# v1.net
KiCad netlist of a schematic drawn in EAGLE
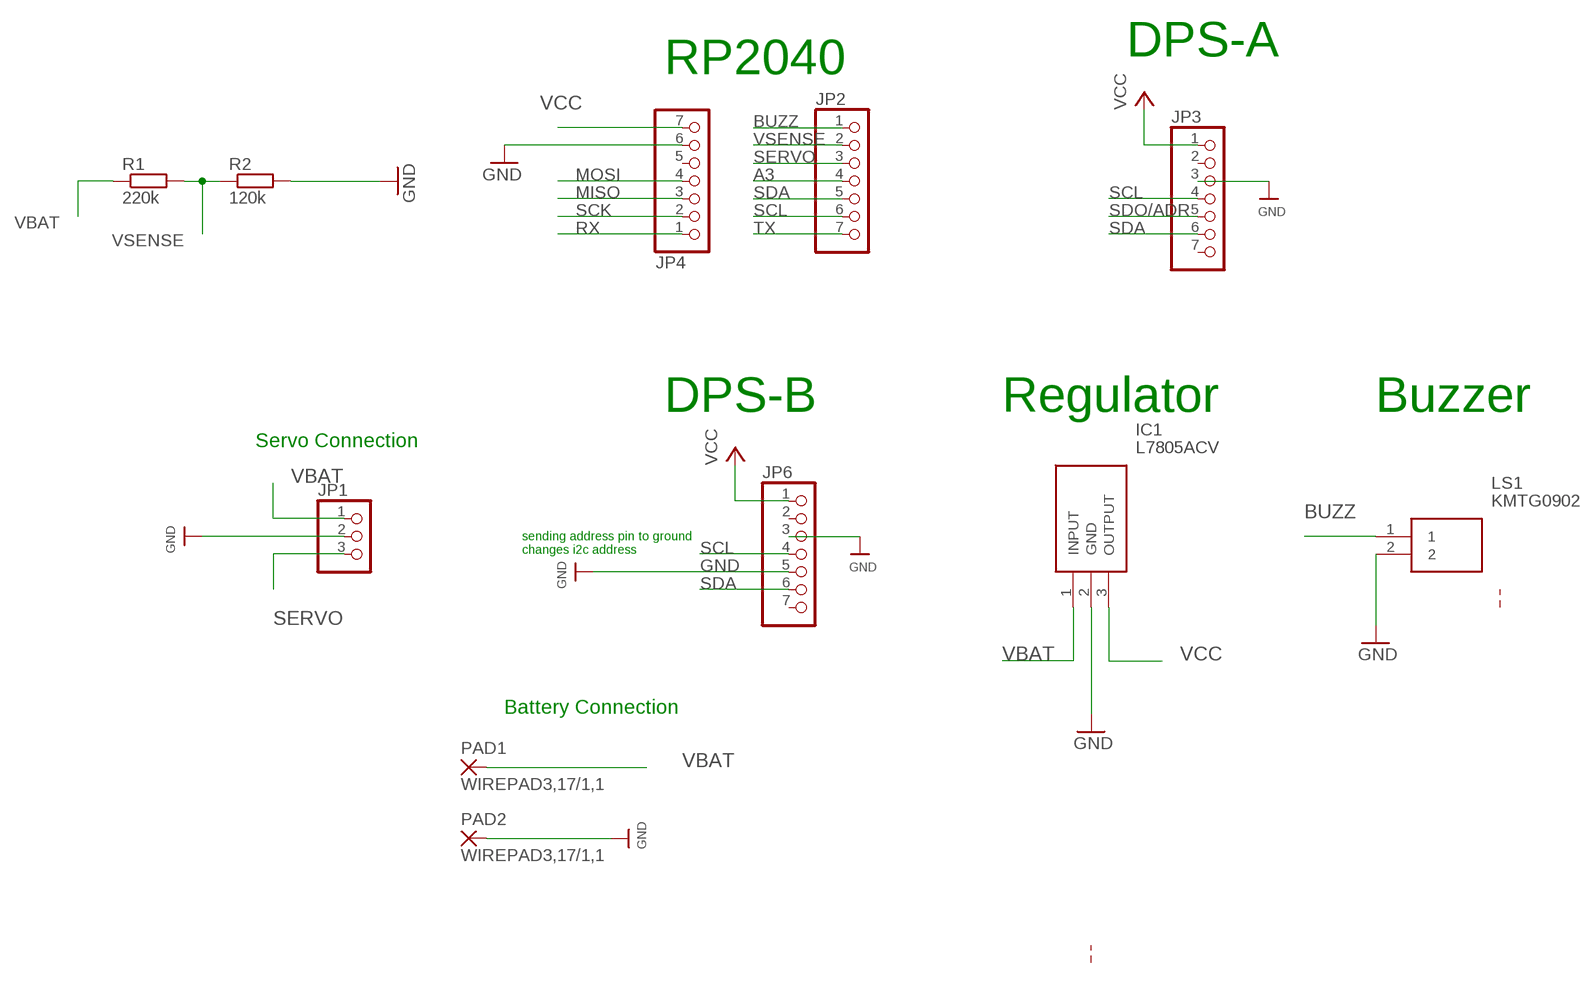
[diagram p0: schematic, sheet 1]

(export (version "E")
  (design (tool "Eeschema 10.0.6"))
  (components
    (comp (ref "IC1")
      (value "L7805ACV")
      (footprint "eagle-import:TO255P460X1020X2008-3P")
      (fields (field (name "RS_PART_NUMBER") "2988508P"))
      (libsource (lib "eagle-import") (part "L7805ACV"))
    )
    (comp (ref "JP1")
      (value "PINHD-1X3")
      (footprint "eagle-import:1X03")
      (libsource (lib "eagle-import") (part "PINHD-1X3"))
    )
    (comp (ref "JP2")
      (value "HEADER-1X7")
      (footprint "eagle-import:1X07_OVAL")
      (libsource (lib "eagle-import") (part "HEADER-1X7"))
    )
    (comp (ref "JP3")
      (value "HEADER-1X770MIL")
      (footprint "eagle-import:1X07_ROUND_70")
      (libsource (lib "eagle-import") (part "HEADER-1X770MIL"))
    )
    (comp (ref "JP4")
      (value "HEADER-1X7")
      (footprint "eagle-import:1X07_OVAL")
      (libsource (lib "eagle-import") (part "HEADER-1X7"))
    )
    (comp (ref "JP6")
      (value "HEADER-1X770MIL")
      (footprint "eagle-import:1X07_ROUND_70")
      (libsource (lib "eagle-import") (part "HEADER-1X770MIL"))
    )
    (comp (ref "LS1")
      (value "KMTG0902")
      (footprint "eagle-import:KMTG0902")
      (fields (field (name "RS_PART_NUMBER") "1812715"))
      (libsource (lib "eagle-import") (part "KMTG0902"))
    )
    (comp (ref "PAD1")
      (value "WIREPAD3,17/1,1")
      (footprint "eagle-import:3,17_1,1")
      (libsource (lib "eagle-import") (part "WIREPAD3,17/1,1"))
    )
    (comp (ref "PAD2")
      (value "WIREPAD3,17/1,1")
      (footprint "eagle-import:3,17_1,1")
      (libsource (lib "eagle-import") (part "WIREPAD3,17/1,1"))
    )
    (comp (ref "R1")
      (value "220k")
      (footprint "eagle-import:0204_5")
      (libsource (lib "eagle-import") (part "R-EU_0204/5"))
    )
    (comp (ref "R2")
      (value "120k")
      (footprint "eagle-import:0204_5")
      (libsource (lib "eagle-import") (part "R-EU_0204/5"))
    )
  )
  (nets
    (net (code "1") (name "/A3") (class "Default")
      (node (ref "JP2") (pin "4") (pinfunction "4_4") (pintype "passive"))
    )
    (net (code "2") (name "/BUZZ") (class "Default")
      (node (ref "JP2") (pin "1") (pinfunction "1_1") (pintype "passive"))
      (node (ref "LS1") (pin "1") (pinfunction "1_1") (pintype "bidirectional"))
    )
    (net (code "3") (name "/MISO") (class "Default")
      (node (ref "JP4") (pin "3") (pinfunction "3_3") (pintype "passive"))
    )
    (net (code "4") (name "/MOSI") (class "Default")
      (node (ref "JP4") (pin "4") (pinfunction "4_4") (pintype "passive"))
    )
    (net (code "5") (name "/RX") (class "Default")
      (node (ref "JP4") (pin "1") (pinfunction "1_1") (pintype "passive"))
    )
    (net (code "6") (name "/SCK") (class "Default")
      (node (ref "JP4") (pin "2") (pinfunction "2_2") (pintype "passive"))
    )
    (net (code "7") (name "/SCL") (class "Default")
      (node (ref "JP2") (pin "6") (pinfunction "6_6") (pintype "passive"))
      (node (ref "JP3") (pin "4") (pinfunction "4_4") (pintype "passive"))
      (node (ref "JP6") (pin "4") (pinfunction "4_4") (pintype "passive"))
    )
    (net (code "8") (name "/SDA") (class "Default")
      (node (ref "JP2") (pin "5") (pinfunction "5_5") (pintype "passive"))
      (node (ref "JP3") (pin "6") (pinfunction "6_6") (pintype "passive"))
      (node (ref "JP6") (pin "6") (pinfunction "6_6") (pintype "passive"))
    )
    (net (code "9") (name "/SDO{slash}ADR") (class "Default")
      (node (ref "JP3") (pin "5") (pinfunction "5_5") (pintype "passive"))
    )
    (net (code "10") (name "/SERVO") (class "Default")
      (node (ref "JP1") (pin "3") (pinfunction "3_3") (pintype "passive"))
      (node (ref "JP2") (pin "3") (pinfunction "3_3") (pintype "passive"))
    )
    (net (code "11") (name "/TX") (class "Default")
      (node (ref "JP2") (pin "7") (pinfunction "7_7") (pintype "passive"))
    )
    (net (code "12") (name "/VBAT") (class "Default")
      (node (ref "IC1") (pin "1") (pinfunction "INPUT_1") (pintype "bidirectional"))
      (node (ref "JP1") (pin "1") (pinfunction "1_1") (pintype "passive"))
      (node (ref "PAD1") (pin "1") (pinfunction "P_1") (pintype "passive"))
      (node (ref "R1") (pin "1") (pinfunction "1_1") (pintype "passive"))
    )
    (net (code "13") (name "/VSENSE") (class "Default")
      (node (ref "JP2") (pin "2") (pinfunction "2_2") (pintype "passive"))
      (node (ref "R1") (pin "2") (pinfunction "2_2") (pintype "passive"))
      (node (ref "R2") (pin "1") (pinfunction "1_1") (pintype "passive"))
    )
    (net (code "14") (name "GND") (class "Default")
      (node (ref "IC1") (pin "2") (pinfunction "GND_2") (pintype "bidirectional"))
      (node (ref "JP1") (pin "2") (pinfunction "2_2") (pintype "passive"))
      (node (ref "JP3") (pin "3") (pinfunction "3_3") (pintype "passive"))
      (node (ref "JP4") (pin "6") (pinfunction "6_6") (pintype "passive"))
      (node (ref "JP6") (pin "3") (pinfunction "3_3") (pintype "passive"))
      (node (ref "JP6") (pin "5") (pinfunction "5_5") (pintype "passive"))
      (node (ref "LS1") (pin "2") (pinfunction "2_2") (pintype "bidirectional"))
      (node (ref "PAD2") (pin "1") (pinfunction "P_1") (pintype "passive"))
      (node (ref "R2") (pin "2") (pinfunction "2_2") (pintype "passive"))
    )
    (net (code "15") (name "VCC") (class "Default")
      (node (ref "IC1") (pin "3") (pinfunction "OUTPUT_3") (pintype "bidirectional"))
      (node (ref "JP3") (pin "1") (pinfunction "1_1") (pintype "passive"))
      (node (ref "JP4") (pin "7") (pinfunction "7_7") (pintype "passive"))
      (node (ref "JP6") (pin "1") (pinfunction "1_1") (pintype "passive"))
    )
    (net (code "16") (name "unconnected-(JP3-Pad2)") (class "Default")
      (node (ref "JP3") (pin "2") (pinfunction "2_2") (pintype "passive"))
    )
    (net (code "17") (name "unconnected-(JP3-Pad7)") (class "Default")
      (node (ref "JP3") (pin "7") (pinfunction "7_7") (pintype "passive"))
    )
    (net (code "18") (name "unconnected-(JP4-Pad5)") (class "Default")
      (node (ref "JP4") (pin "5") (pinfunction "5_5") (pintype "passive"))
    )
    (net (code "19") (name "unconnected-(JP6-Pad2)") (class "Default")
      (node (ref "JP6") (pin "2") (pinfunction "2_2") (pintype "passive"))
    )
    (net (code "20") (name "unconnected-(JP6-Pad7)") (class "Default")
      (node (ref "JP6") (pin "7") (pinfunction "7_7") (pintype "passive"))
    )
  )
)
